# Reconstruction_Filter.net
KiCad netlist of a schematic drawn in Altium Designer
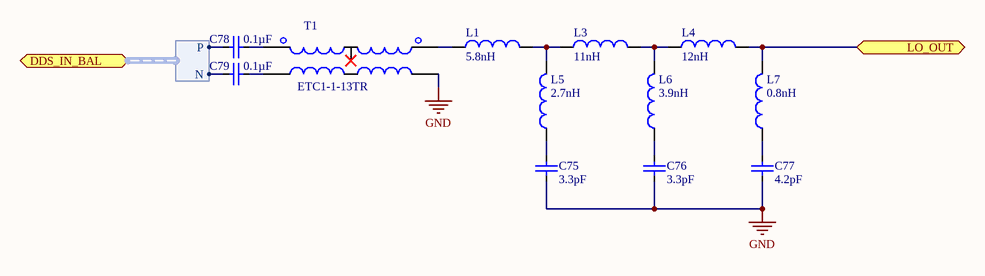
[diagram p0: Reconstruction_Filter.SchDoc]

(export (version "E")
  (design (tool "Eeschema 10.0.6"))
  (components
    (comp (ref "C75")
      (value "3.3pF")
      (footprint "CAPC1005X50L25N")
      (description "CAP CER 3.3PF 50V NP0 0402")
      (fields
        (field (name "MANUFACTURER") "Murata Electronics North America")
        (field (name "MANUFACTURER PART NUMBER") "GJM1555C1H3R3WB01D")
      )
      (libsource (lib "mechanart_oshw") (part "CapSMT"))
    )
    (comp (ref "C76")
      (value "3.3pF")
      (footprint "CAPC1005X50L25N")
      (description "CAP CER 3.3PF 50V NP0 0402")
      (fields
        (field (name "MANUFACTURER") "Murata Electronics North America")
        (field (name "MANUFACTURER PART NUMBER") "GJM1555C1H3R3WB01D")
      )
      (libsource (lib "mechanart_oshw") (part "CapSMT"))
    )
    (comp (ref "C77")
      (value "4.2pF")
      (footprint "CAPC1005X50L25N")
      (description "CAP CER 4.2PF 50V NP0 0402")
      (fields
        (field (name "MANUFACTURER") "Murata Electronics North America")
        (field (name "MANUFACTURER PART NUMBER") "GJM1555C1H4R2BB01D")
      )
      (libsource (lib "mechanart_oshw") (part "CapSMT"))
    )
    (comp (ref "C78")
      (value "0.1µF")
      (footprint "CAPC1005X50L25N")
      (description "CAP CER 0.1UF 50V X7R 0402")
      (fields
        (field (name "MANUFACTURER") "Murata Electronics North America")
        (field (name "MANUFACTURER PART NUMBER") "GRM155R71H104KE14D")
      )
      (libsource (lib "mechanart_oshw") (part "CapSMT"))
    )
    (comp (ref "C79")
      (value "0.1µF")
      (footprint "CAPC1005X50L25N")
      (description "CAP CER 0.1UF 50V X7R 0402")
      (fields
        (field (name "MANUFACTURER") "Murata Electronics North America")
        (field (name "MANUFACTURER PART NUMBER") "GRM155R71H104KE14D")
      )
      (libsource (lib "mechanart_oshw") (part "CapSMT"))
    )
    (comp (ref "L1")
      (value "5.8nH")
      (footprint "INDC1006X18L23N")
      (description "FIXED IND 5.8NH")
      (fields
        (field (name "MANUFACTURER") "Coilcraft")
        (field (name "MANUFACTURER PART NUMBER") "0402PA-5N8XGLU")
      )
      (libsource (lib "mechanart_oshw") (part "Inductor"))
    )
    (comp (ref "L3")
      (value "11nH")
      (footprint "INDC1006X18L23N")
      (libsource (lib "mechanart_oshw") (part "Inductor"))
    )
    (comp (ref "L4")
      (value "12nH")
      (footprint "INDC1006X18L23N")
      (libsource (lib "mechanart_oshw") (part "Inductor"))
    )
    (comp (ref "L5")
      (value "2.7nH")
      (footprint "INDC1006X18L23N")
      (libsource (lib "mechanart_oshw") (part "Inductor"))
    )
    (comp (ref "L6")
      (value "3.9nH")
      (footprint "INDC1006X18L23N")
      (libsource (lib "mechanart_oshw") (part "Inductor"))
    )
    (comp (ref "L7")
      (value "0.8nH")
      (footprint "INDC1006X18L23N")
      (libsource (lib "mechanart_oshw") (part "Inductor"))
    )
    (comp (ref "T1")
      (value "ETC1-1-13TR")
      (footprint "AT1521")
      (description "TRANSFORMER")
      (fields (field (name "MANUFACTURER") "M/A-Com Technology Solutions"))
      (libsource (lib "mechanart_oshw") (part "TLT"))
    )
  )
  (nets
    (net (code "2") (name "/LO_OUT") (class "Default")
      (node (ref "L4") (pin "2") (pinfunction "2_2") (pintype "passive"))
      (node (ref "L7") (pin "2") (pinfunction "2_2") (pintype "passive"))
    )
    (net (code "3") (name "/N") (class "Default")
      (node (ref "C79") (pin "1") (pinfunction "1_1") (pintype "passive"))
    )
    (net (code "4") (name "/P") (class "Default")
      (node (ref "C78") (pin "1") (pinfunction "1_1") (pintype "passive"))
    )
    (net (code "6") (name "GND") (class "Default")
      (node (ref "C75") (pin "2") (pinfunction "2_2") (pintype "passive"))
      (node (ref "C76") (pin "2") (pinfunction "2_2") (pintype "passive"))
      (node (ref "C77") (pin "2") (pinfunction "2_2") (pintype "passive"))
      (node (ref "T1") (pin "3") (pinfunction "SECONDARY_3") (pintype "passive"))
    )
    (net (code "7") (name "Net-(C75-Pad1)") (class "Default")
      (node (ref "C75") (pin "1") (pinfunction "1_1") (pintype "passive"))
      (node (ref "L5") (pin "1") (pinfunction "1_1") (pintype "passive"))
    )
    (net (code "8") (name "Net-(C76-Pad1)") (class "Default")
      (node (ref "C76") (pin "1") (pinfunction "1_1") (pintype "passive"))
      (node (ref "L6") (pin "1") (pinfunction "1_1") (pintype "passive"))
    )
    (net (code "9") (name "Net-(C77-Pad1)") (class "Default")
      (node (ref "C77") (pin "1") (pinfunction "1_1") (pintype "passive"))
      (node (ref "L7") (pin "1") (pinfunction "1_1") (pintype "passive"))
    )
    (net (code "10") (name "Net-(L1-Pad2)") (class "Default")
      (node (ref "L1") (pin "2") (pinfunction "2_2") (pintype "passive"))
      (node (ref "L3") (pin "1") (pinfunction "1_1") (pintype "passive"))
      (node (ref "L5") (pin "2") (pinfunction "2_2") (pintype "passive"))
    )
    (net (code "11") (name "Net-(L3-Pad2)") (class "Default")
      (node (ref "L3") (pin "2") (pinfunction "2_2") (pintype "passive"))
      (node (ref "L4") (pin "1") (pinfunction "1_1") (pintype "passive"))
      (node (ref "L6") (pin "2") (pinfunction "2_2") (pintype "passive"))
    )
    (net (code "12") (name "Net-(T1-PRIMARY)") (class "Default")
      (node (ref "C79") (pin "2") (pinfunction "2_2") (pintype "passive"))
      (node (ref "T1") (pin "4") (pinfunction "PRIMARY_4") (pintype "passive"))
    )
    (net (code "13") (name "Net-(T1-PRIMARY_DOT)") (class "Default")
      (node (ref "C78") (pin "2") (pinfunction "2_2") (pintype "passive"))
      (node (ref "T1") (pin "6") (pinfunction "PRIMARY_DOT_6") (pintype "passive"))
    )
    (net (code "14") (name "Net-(T1-SECONDARY_DOT)") (class "Default")
      (node (ref "L1") (pin "1") (pinfunction "1_1") (pintype "passive"))
      (node (ref "T1") (pin "1") (pinfunction "SECONDARY_DOT_1") (pintype "passive"))
    )
    (net (code "15") (name "unconnected-(T1-NO_CONNECT-Pad2)") (class "Default")
      (node (ref "T1") (pin "2") (pinfunction "NO_CONNECT_2") (pintype "passive+no_connect"))
    )
  )
)
